# 14_FPGA_SPI.net
KiCad netlist of a schematic drawn in Altium Designer
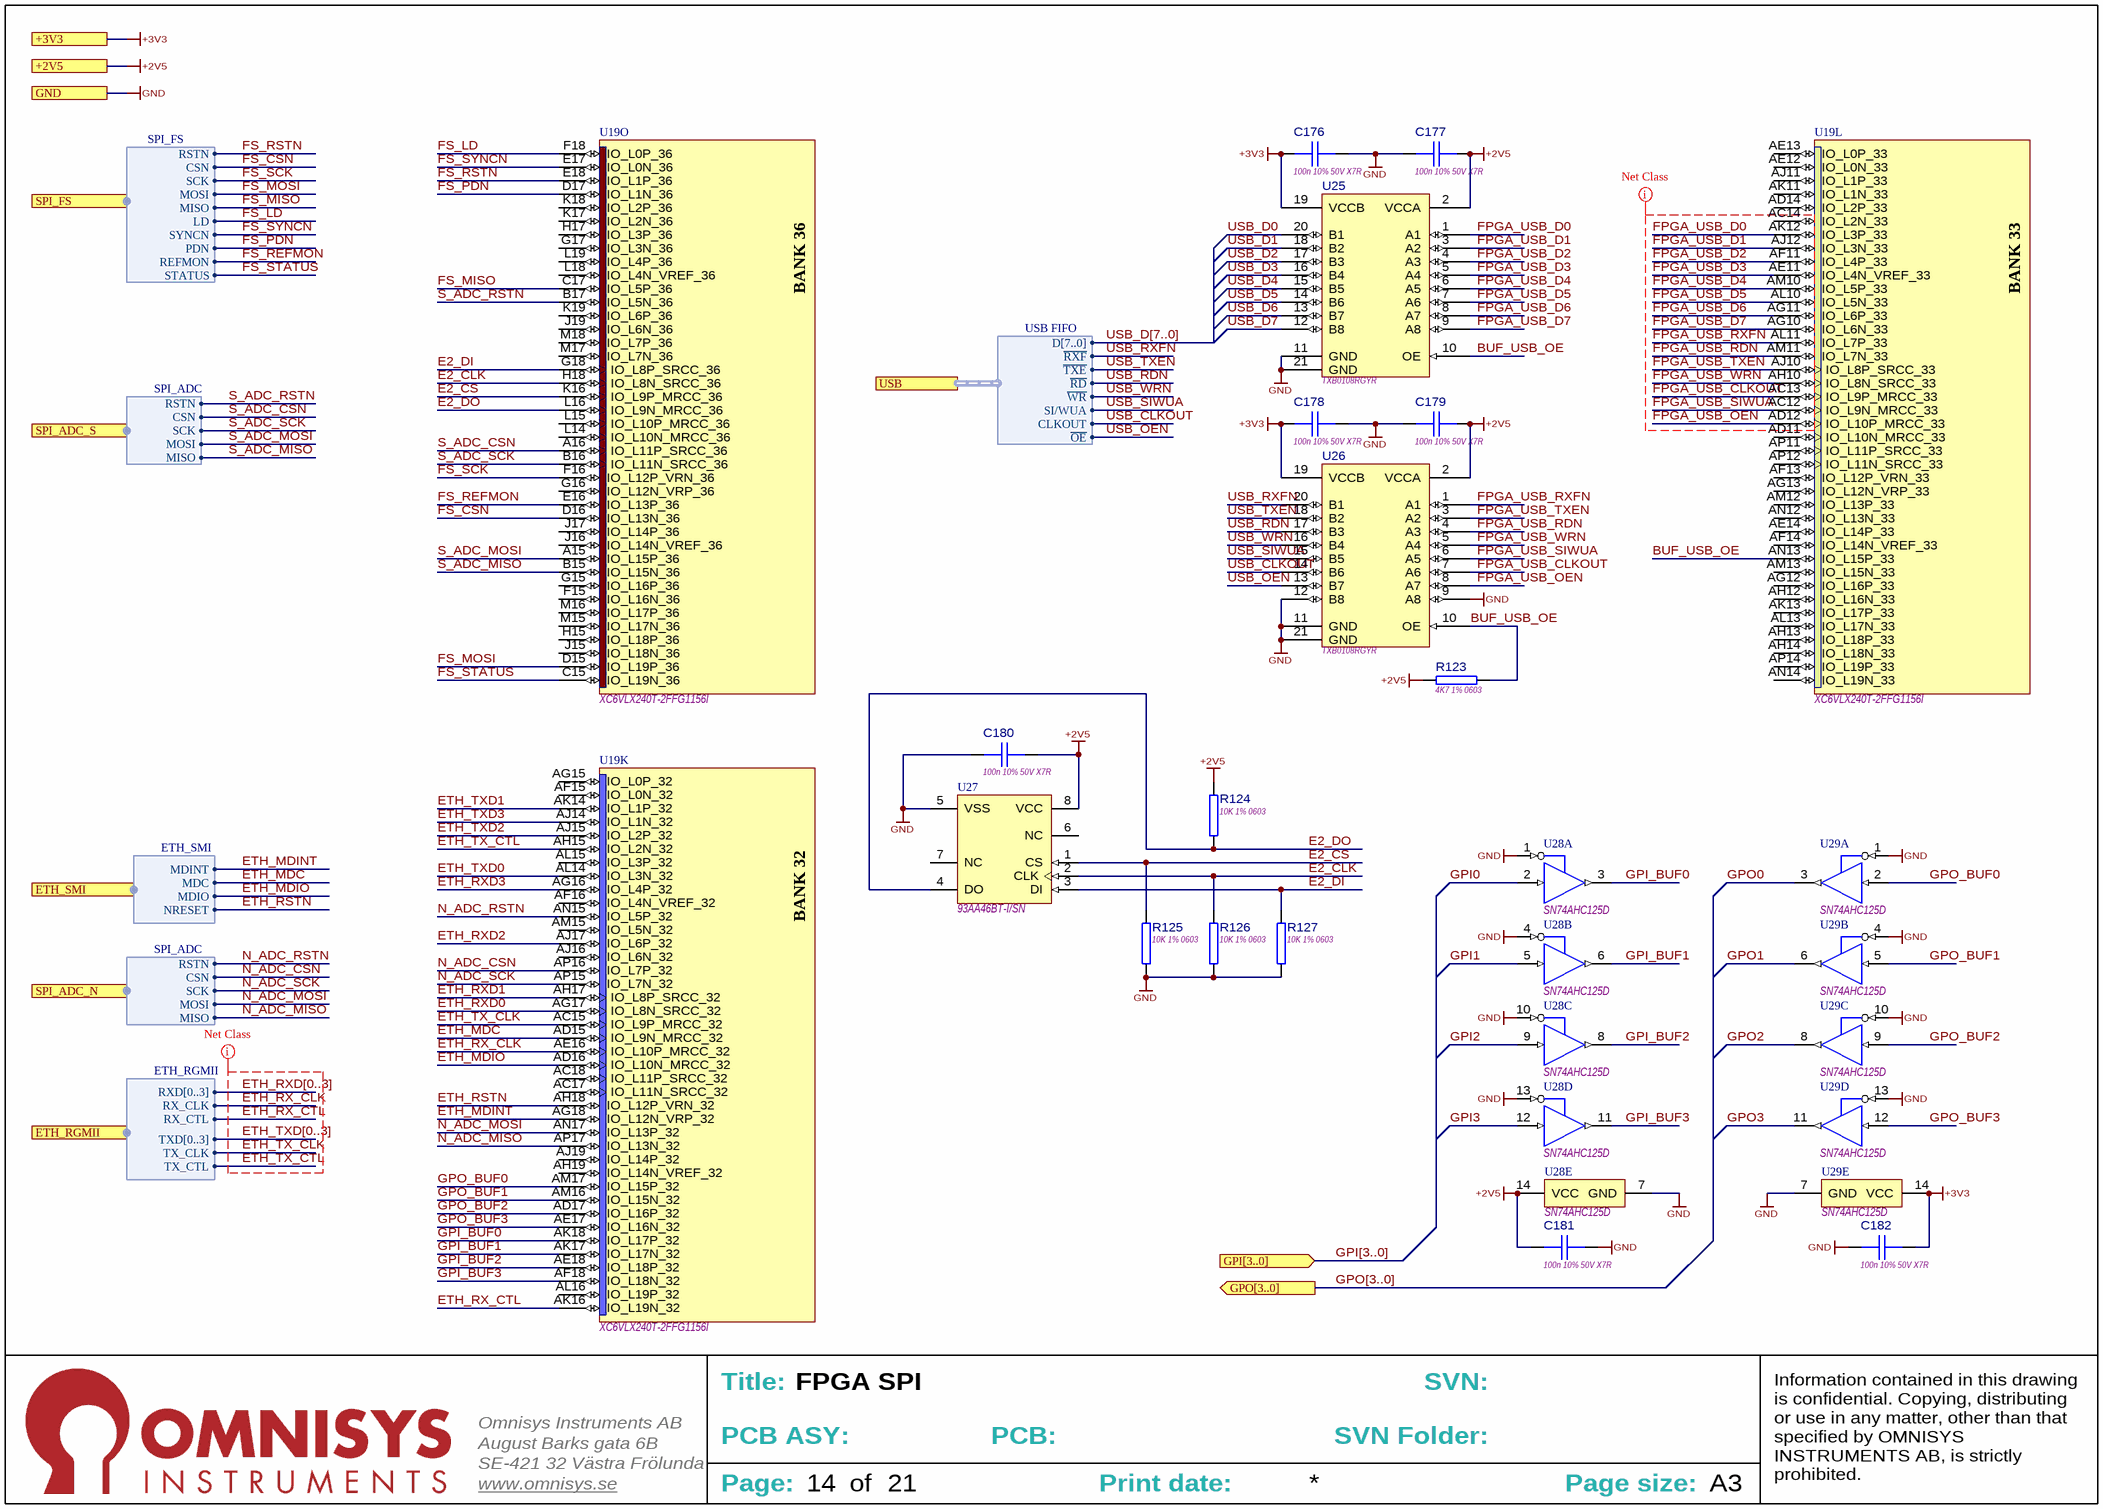
[diagram p0: [14] FPGA_SPI.SchDoc]

(export (version "E")
  (design (tool "Eeschema 10.0.6"))
  (components
    (comp (ref "C176")
      (value "100n 10% 50V X7R")
      (footprint "CAPC1608X90N")
      (description "Ceramic Chip Capacitor, 0603/1608")
      (fields (field (name "TOLERANCE") "10%"))
      (libsource (lib "Omnisys Vault") (part "CAP-2PIN"))
    )
    (comp (ref "C177")
      (value "100n 10% 50V X7R")
      (footprint "CAPC1608X90N")
      (description "Ceramic Chip Capacitor, 0603/1608")
      (fields (field (name "TOLERANCE") "10%"))
      (libsource (lib "Omnisys Vault") (part "CAP-2PIN"))
    )
    (comp (ref "C178")
      (value "100n 10% 50V X7R")
      (footprint "CAPC1608X90N")
      (description "Ceramic Chip Capacitor, 0603/1608")
      (fields (field (name "TOLERANCE") "10%"))
      (libsource (lib "Omnisys Vault") (part "CAP-2PIN"))
    )
    (comp (ref "C179")
      (value "100n 10% 50V X7R")
      (footprint "CAPC1608X90N")
      (description "Ceramic Chip Capacitor, 0603/1608")
      (fields (field (name "TOLERANCE") "10%"))
      (libsource (lib "Omnisys Vault") (part "CAP-2PIN"))
    )
    (comp (ref "C180")
      (value "100n 10% 50V X7R")
      (footprint "CAPC1608X90N")
      (description "Ceramic Chip Capacitor, 0603/1608")
      (fields (field (name "TOLERANCE") "10%"))
      (libsource (lib "Omnisys Vault") (part "CAP-2PIN"))
    )
    (comp (ref "C181")
      (value "100n 10% 50V X7R")
      (footprint "CAPC1608X90N")
      (description "Ceramic Chip Capacitor, 0603/1608")
      (fields (field (name "TOLERANCE") "10%"))
      (libsource (lib "Omnisys Vault") (part "CAP-2PIN"))
    )
    (comp (ref "C182")
      (value "100n 10% 50V X7R")
      (footprint "CAPC1608X90N")
      (description "Ceramic Chip Capacitor, 0603/1608")
      (fields (field (name "TOLERANCE") "10%"))
      (libsource (lib "Omnisys Vault") (part "CAP-2PIN"))
    )
    (comp (ref "R123")
      (value "4K7 1% 0603")
      (footprint "RESC1608N")
      (description "Thick film Chip Resistor, 0603/1608")
      (fields (field (name "POWER") "100mW") (field (name "TOLERANCE") "1%"))
      (libsource (lib "Omnisys Vault") (part "RES-2PIN"))
    )
    (comp (ref "R124")
      (value "10K 1% 0603")
      (footprint "RESC1608N")
      (description "Thick film Chip Resistor, 0603/1608")
      (fields (field (name "POWER") "100mW") (field (name "TOLERANCE") "1%"))
      (libsource (lib "Omnisys Vault") (part "RES-2PIN"))
    )
    (comp (ref "R125")
      (value "10K 1% 0603")
      (footprint "RESC1608N")
      (description "Thick film Chip Resistor, 0603/1608")
      (fields (field (name "POWER") "100mW") (field (name "TOLERANCE") "1%"))
      (libsource (lib "Omnisys Vault") (part "RES-2PIN"))
    )
    (comp (ref "R126")
      (value "10K 1% 0603")
      (footprint "RESC1608N")
      (description "Thick film Chip Resistor, 0603/1608")
      (fields (field (name "POWER") "100mW") (field (name "TOLERANCE") "1%"))
      (libsource (lib "Omnisys Vault") (part "RES-2PIN"))
    )
    (comp (ref "R127")
      (value "10K 1% 0603")
      (footprint "RESC1608N")
      (description "Thick film Chip Resistor, 0603/1608")
      (fields (field (name "POWER") "100mW") (field (name "TOLERANCE") "1%"))
      (libsource (lib "Omnisys Vault") (part "RES-2PIN"))
    )
    (comp (ref "U19")
      (value "XC6VLX240T-2FFG1156I")
      (footprint "FFG1156")
      (description "FPGA Virtex-6 LXT Family 241152 Cells 40nm (CMOS) Technology 1V 1156-Pin FCBGA")
      (libsource (lib "Omnisys Vault") (part "FPGA-XVR6-XC6VXXXXXT-GA1156"))
    )
    (comp (ref "U25")
      (value "TXB0108RGYR")
      (footprint "TXB0108RGYR")
      (description "TEXAS INSTRUMENTS   TXB0108RGYR   TRANSLATOR, VOLTAGE, 8BIT, 20VQFN")
      (libsource (lib "Omnisys Vault") (part "TXB0108RGYR"))
    )
    (comp (ref "U26")
      (value "TXB0108RGYR")
      (footprint "TXB0108RGYR")
      (description "TEXAS INSTRUMENTS   TXB0108RGYR   TRANSLATOR, VOLTAGE, 8BIT, 20VQFN")
      (libsource (lib "Omnisys Vault") (part "TXB0108RGYR"))
    )
    (comp (ref "U27")
      (value "93AA46BT-I/SN")
      (footprint "SOIC127P600X175-8N")
      (description "IC EEPROM 1KBIT 2MHZ 8SOIC")
      (libsource (lib "Omnisys Vault") (part "MEM-SEEPROM-93AA46B-P-8"))
    )
    (comp (ref "U28")
      (value "SN74AHC125D")
      (footprint "SOIC127P600X175-14N")
      (description "Buffer/Line Driver 4-CH Non-Inverting 3-ST CMOS 14-Pin SOIC Tube")
      (libsource (lib "Omnisys Vault") (part "SN74AHC125D"))
    )
    (comp (ref "U29")
      (value "SN74AHC125D")
      (footprint "SOIC127P600X175-14L")
      (description "Buffer/Line Driver 4-CH Non-Inverting 3-ST CMOS 14-Pin SOIC Tube")
      (libsource (lib "") (part "SN74AHC125D_1"))
    )
  )
  (nets
    (net (code "7") (name "+2V5") (class "Default")
      (node (ref "C177") (pin "2") (pinfunction "2_2") (pintype "passive"))
      (node (ref "C179") (pin "2") (pinfunction "2_2") (pintype "passive"))
      (node (ref "C180") (pin "2") (pinfunction "2_2") (pintype "passive"))
      (node (ref "C181") (pin "1") (pinfunction "1_1") (pintype "passive"))
      (node (ref "R123") (pin "2") (pinfunction "2_2") (pintype "passive"))
      (node (ref "R124") (pin "2") (pinfunction "2_2") (pintype "passive"))
      (node (ref "U25") (pin "2") (pinfunction "VCCA_2") (pintype "power_in"))
      (node (ref "U26") (pin "2") (pinfunction "VCCA_2") (pintype "power_in"))
      (node (ref "U27") (pin "8") (pinfunction "VCC_8") (pintype "power_in"))
      (node (ref "U28") (pin "14") (pinfunction "VCC_14") (pintype "power_in"))
    )
    (net (code "8") (name "+3V3") (class "Default")
      (node (ref "C176") (pin "1") (pinfunction "1_1") (pintype "passive"))
      (node (ref "C178") (pin "1") (pinfunction "1_1") (pintype "passive"))
      (node (ref "C182") (pin "1") (pinfunction "1_1") (pintype "passive"))
      (node (ref "U25") (pin "19") (pinfunction "VCCB_19") (pintype "power_in"))
      (node (ref "U26") (pin "19") (pinfunction "VCCB_19") (pintype "power_in"))
      (node (ref "U29") (pin "14") (pinfunction "VCC_14") (pintype "power_in"))
    )
    (net (code "9") (name "/BUF_USB_OE") (class "Default")
      (node (ref "R123") (pin "1") (pinfunction "1_1") (pintype "passive"))
      (node (ref "U19") (pin "AN13") (pinfunction "IO_L15P_33_AN13") (pintype "bidirectional"))
      (node (ref "U25") (pin "10") (pinfunction "OE_10") (pintype "input"))
      (node (ref "U26") (pin "10") (pinfunction "OE_10") (pintype "input"))
    )
    (net (code "10") (name "/E2_CLK") (class "Default")
      (node (ref "R126") (pin "2") (pinfunction "2_2") (pintype "passive"))
      (node (ref "U19") (pin "H18") (pinfunction "IO_L8N_SRCC_36_H18") (pintype "bidirectional"))
      (node (ref "U27") (pin "2") (pinfunction "CLK_2") (pintype "input"))
    )
    (net (code "11") (name "/E2_CS") (class "Default")
      (node (ref "R125") (pin "2") (pinfunction "2_2") (pintype "passive"))
      (node (ref "U19") (pin "K16") (pinfunction "IO_L9P_MRCC_36_K16") (pintype "bidirectional"))
      (node (ref "U27") (pin "1") (pinfunction "CS_1") (pintype "input"))
    )
    (net (code "12") (name "/E2_DI") (class "Default")
      (node (ref "R127") (pin "2") (pinfunction "2_2") (pintype "passive"))
      (node (ref "U19") (pin "G18") (pinfunction "IO_L8P_SRCC_36_G18") (pintype "bidirectional"))
      (node (ref "U27") (pin "3") (pinfunction "DI_3") (pintype "input"))
    )
    (net (code "13") (name "/E2_DO") (class "Default")
      (node (ref "R124") (pin "1") (pinfunction "1_1") (pintype "passive"))
      (node (ref "U19") (pin "L16") (pinfunction "IO_L9N_MRCC_36_L16") (pintype "bidirectional"))
      (node (ref "U27") (pin "4") (pinfunction "DO_4") (pintype "tri_state"))
    )
    (net (code "14") (name "/ETH_MDC") (class "Default")
      (node (ref "U19") (pin "AD15") (pinfunction "IO_L9N_MRCC_32_AD15") (pintype "bidirectional"))
    )
    (net (code "15") (name "/ETH_MDINT") (class "Default")
      (node (ref "U19") (pin "AG18") (pinfunction "IO_L12N_VRP_32_AG18") (pintype "bidirectional"))
    )
    (net (code "16") (name "/ETH_MDIO") (class "Default")
      (node (ref "U19") (pin "AD16") (pinfunction "IO_L10N_MRCC_32_AD16") (pintype "bidirectional"))
    )
    (net (code "18") (name "/ETH_RSTN") (class "Default")
      (node (ref "U19") (pin "AH18") (pinfunction "IO_L12P_VRN_32_AH18") (pintype "bidirectional"))
    )
    (net (code "19") (name "/ETH_RXD0") (class "Default")
      (node (ref "U19") (pin "AG17") (pinfunction "IO_L8N_SRCC_32_AG17") (pintype "bidirectional"))
    )
    (net (code "20") (name "/ETH_RXD1") (class "Default")
      (node (ref "U19") (pin "AH17") (pinfunction "IO_L8P_SRCC_32_AH17") (pintype "bidirectional"))
    )
    (net (code "21") (name "/ETH_RXD2") (class "Default")
      (node (ref "U19") (pin "AJ17") (pinfunction "IO_L6P_32_AJ17") (pintype "bidirectional"))
    )
    (net (code "22") (name "/ETH_RXD3") (class "Default")
      (node (ref "U19") (pin "AG16") (pinfunction "IO_L4P_32_AG16") (pintype "bidirectional"))
    )
    (net (code "24") (name "/ETH_RX_CLK") (class "Default")
      (node (ref "U19") (pin "AE16") (pinfunction "IO_L10P_MRCC_32_AE16") (pintype "bidirectional"))
    )
    (net (code "25") (name "/ETH_RX_CTL") (class "Default")
      (node (ref "U19") (pin "AK16") (pinfunction "IO_L19N_32_AK16") (pintype "bidirectional"))
    )
    (net (code "26") (name "/ETH_TXD0") (class "Default")
      (node (ref "U19") (pin "AL14") (pinfunction "IO_L3N_32_AL14") (pintype "bidirectional"))
    )
    (net (code "27") (name "/ETH_TXD1") (class "Default")
      (node (ref "U19") (pin "AK14") (pinfunction "IO_L1P_32_AK14") (pintype "bidirectional"))
    )
    (net (code "28") (name "/ETH_TXD2") (class "Default")
      (node (ref "U19") (pin "AJ15") (pinfunction "IO_L2P_32_AJ15") (pintype "bidirectional"))
    )
    (net (code "29") (name "/ETH_TXD3") (class "Default")
      (node (ref "U19") (pin "AJ14") (pinfunction "IO_L1N_32_AJ14") (pintype "bidirectional"))
    )
    (net (code "30") (name "/ETH_TX_CLK") (class "Default")
      (node (ref "U19") (pin "AC15") (pinfunction "IO_L9P_MRCC_32_AC15") (pintype "bidirectional"))
    )
    (net (code "31") (name "/ETH_TX_CTL") (class "Default")
      (node (ref "U19") (pin "AH15") (pinfunction "IO_L2N_32_AH15") (pintype "bidirectional"))
    )
    (net (code "32") (name "/FPGA_USB_CLKOUT") (class "Default")
      (node (ref "U19") (pin "AC13") (pinfunction "IO_L9P_MRCC_33_AC13") (pintype "bidirectional"))
      (node (ref "U26") (pin "7") (pinfunction "A6_7") (pintype "bidirectional"))
    )
    (net (code "33") (name "/FPGA_USB_D0") (class "Default")
      (node (ref "U19") (pin "AK12") (pinfunction "IO_L3P_33_AK12") (pintype "bidirectional"))
      (node (ref "U25") (pin "1") (pinfunction "A1_1") (pintype "bidirectional"))
    )
    (net (code "34") (name "/FPGA_USB_D1") (class "Default")
      (node (ref "U19") (pin "AJ12") (pinfunction "IO_L3N_33_AJ12") (pintype "bidirectional"))
      (node (ref "U25") (pin "3") (pinfunction "A2_3") (pintype "bidirectional"))
    )
    (net (code "35") (name "/FPGA_USB_D2") (class "Default")
      (node (ref "U19") (pin "AF11") (pinfunction "IO_L4P_33_AF11") (pintype "bidirectional"))
      (node (ref "U25") (pin "4") (pinfunction "A3_4") (pintype "bidirectional"))
    )
    (net (code "36") (name "/FPGA_USB_D3") (class "Default")
      (node (ref "U19") (pin "AE11") (pinfunction "IO_L4N_VREF_33_AE11") (pintype "bidirectional"))
      (node (ref "U25") (pin "5") (pinfunction "A4_5") (pintype "bidirectional"))
    )
    (net (code "37") (name "/FPGA_USB_D4") (class "Default")
      (node (ref "U19") (pin "AM10") (pinfunction "IO_L5P_33_AM10") (pintype "bidirectional"))
      (node (ref "U25") (pin "6") (pinfunction "A5_6") (pintype "bidirectional"))
    )
    (net (code "38") (name "/FPGA_USB_D5") (class "Default")
      (node (ref "U19") (pin "AL10") (pinfunction "IO_L5N_33_AL10") (pintype "bidirectional"))
      (node (ref "U25") (pin "7") (pinfunction "A6_7") (pintype "bidirectional"))
    )
    (net (code "39") (name "/FPGA_USB_D6") (class "Default")
      (node (ref "U19") (pin "AG11") (pinfunction "IO_L6P_33_AG11") (pintype "bidirectional"))
      (node (ref "U25") (pin "8") (pinfunction "A7_8") (pintype "bidirectional"))
    )
    (net (code "40") (name "/FPGA_USB_D7") (class "Default")
      (node (ref "U19") (pin "AG10") (pinfunction "IO_L6N_33_AG10") (pintype "bidirectional"))
      (node (ref "U25") (pin "9") (pinfunction "A8_9") (pintype "bidirectional"))
    )
    (net (code "41") (name "/FPGA_USB_OEN") (class "Default")
      (node (ref "U19") (pin "AD12") (pinfunction "IO_L10P_MRCC_33_AD12") (pintype "bidirectional"))
      (node (ref "U26") (pin "8") (pinfunction "A7_8") (pintype "bidirectional"))
    )
    (net (code "42") (name "/FPGA_USB_RDN") (class "Default")
      (node (ref "U19") (pin "AM11") (pinfunction "IO_L7N_33_AM11") (pintype "bidirectional"))
      (node (ref "U26") (pin "4") (pinfunction "A3_4") (pintype "bidirectional"))
    )
    (net (code "43") (name "/FPGA_USB_RXFN") (class "Default")
      (node (ref "U19") (pin "AL11") (pinfunction "IO_L7P_33_AL11") (pintype "bidirectional"))
      (node (ref "U26") (pin "1") (pinfunction "A1_1") (pintype "bidirectional"))
    )
    (net (code "44") (name "/FPGA_USB_SIWUA") (class "Default")
      (node (ref "U19") (pin "AC12") (pinfunction "IO_L9N_MRCC_33_AC12") (pintype "bidirectional"))
      (node (ref "U26") (pin "6") (pinfunction "A5_6") (pintype "bidirectional"))
    )
    (net (code "45") (name "/FPGA_USB_TXEN") (class "Default")
      (node (ref "U19") (pin "AJ10") (pinfunction "IO_L8P_SRCC_33_AJ10") (pintype "bidirectional"))
      (node (ref "U26") (pin "3") (pinfunction "A2_3") (pintype "bidirectional"))
    )
    (net (code "46") (name "/FPGA_USB_WRN") (class "Default")
      (node (ref "U19") (pin "AH10") (pinfunction "IO_L8N_SRCC_33_AH10") (pintype "bidirectional"))
      (node (ref "U26") (pin "5") (pinfunction "A4_5") (pintype "bidirectional"))
    )
    (net (code "47") (name "/FS_CSN") (class "Default")
      (node (ref "U19") (pin "D16") (pinfunction "IO_L13N_36_D16") (pintype "bidirectional"))
    )
    (net (code "48") (name "/FS_LD") (class "Default")
      (node (ref "U19") (pin "F18") (pinfunction "IO_L0P_36_F18") (pintype "bidirectional"))
    )
    (net (code "49") (name "/FS_MISO") (class "Default")
      (node (ref "U19") (pin "C17") (pinfunction "IO_L5P_36_C17") (pintype "bidirectional"))
    )
    (net (code "50") (name "/FS_MOSI") (class "Default")
      (node (ref "U19") (pin "D15") (pinfunction "IO_L19P_36_D15") (pintype "bidirectional"))
    )
    (net (code "51") (name "/FS_PDN") (class "Default")
      (node (ref "U19") (pin "D17") (pinfunction "IO_L1N_36_D17") (pintype "bidirectional"))
    )
    (net (code "52") (name "/FS_REFMON") (class "Default")
      (node (ref "U19") (pin "E16") (pinfunction "IO_L13P_36_E16") (pintype "bidirectional"))
    )
    (net (code "53") (name "/FS_RSTN") (class "Default")
      (node (ref "U19") (pin "E18") (pinfunction "IO_L1P_36_E18") (pintype "bidirectional"))
    )
    (net (code "54") (name "/FS_SCK") (class "Default")
      (node (ref "U19") (pin "F16") (pinfunction "IO_L12P_VRN_36_F16") (pintype "bidirectional"))
    )
    (net (code "55") (name "/FS_STATUS") (class "Default")
      (node (ref "U19") (pin "C15") (pinfunction "IO_L19N_36_C15") (pintype "bidirectional"))
    )
    (net (code "56") (name "/FS_SYNCN") (class "Default")
      (node (ref "U19") (pin "E17") (pinfunction "IO_L0N_36_E17") (pintype "bidirectional"))
    )
    (net (code "57") (name "/GPI0") (class "Default")
      (node (ref "U28") (pin "2") (pinfunction "1A_2") (pintype "input"))
    )
    (net (code "58") (name "/GPI1") (class "Default")
      (node (ref "U28") (pin "5") (pinfunction "2A_5") (pintype "input"))
    )
    (net (code "59") (name "/GPI2") (class "Default")
      (node (ref "U28") (pin "9") (pinfunction "3A_9") (pintype "input"))
    )
    (net (code "60") (name "/GPI3") (class "Default")
      (node (ref "U28") (pin "12") (pinfunction "4A_12") (pintype "input"))
    )
    (net (code "62") (name "/GPI_BUF0") (class "Default")
      (node (ref "U19") (pin "AK18") (pinfunction "IO_L17P_32_AK18") (pintype "bidirectional"))
      (node (ref "U28") (pin "3") (pinfunction "1Y_3") (pintype "output"))
    )
    (net (code "63") (name "/GPI_BUF1") (class "Default")
      (node (ref "U19") (pin "AK17") (pinfunction "IO_L17N_32_AK17") (pintype "bidirectional"))
      (node (ref "U28") (pin "6") (pinfunction "2Y_6") (pintype "output"))
    )
    (net (code "64") (name "/GPI_BUF2") (class "Default")
      (node (ref "U19") (pin "AE18") (pinfunction "IO_L18P_32_AE18") (pintype "bidirectional"))
      (node (ref "U28") (pin "8") (pinfunction "3Y_8") (pintype "output"))
    )
    (net (code "65") (name "/GPI_BUF3") (class "Default")
      (node (ref "U19") (pin "AF18") (pinfunction "IO_L18N_32_AF18") (pintype "bidirectional"))
      (node (ref "U28") (pin "11") (pinfunction "4Y_11") (pintype "output"))
    )
    (net (code "66") (name "/GPO0") (class "Default")
      (node (ref "U29") (pin "3") (pinfunction "1Y_3") (pintype "output"))
    )
    (net (code "67") (name "/GPO1") (class "Default")
      (node (ref "U29") (pin "6") (pinfunction "2Y_6") (pintype "output"))
    )
    (net (code "68") (name "/GPO2") (class "Default")
      (node (ref "U29") (pin "8") (pinfunction "3Y_8") (pintype "output"))
    )
    (net (code "69") (name "/GPO3") (class "Default")
      (node (ref "U29") (pin "11") (pinfunction "4Y_11") (pintype "output"))
    )
    (net (code "71") (name "/GPO_BUF0") (class "Default")
      (node (ref "U19") (pin "AM17") (pinfunction "IO_L15P_32_AM17") (pintype "bidirectional"))
      (node (ref "U29") (pin "2") (pinfunction "1A_2") (pintype "input"))
    )
    (net (code "72") (name "/GPO_BUF1") (class "Default")
      (node (ref "U19") (pin "AM16") (pinfunction "IO_L15N_32_AM16") (pintype "bidirectional"))
      (node (ref "U29") (pin "5") (pinfunction "2A_5") (pintype "input"))
    )
    (net (code "73") (name "/GPO_BUF2") (class "Default")
      (node (ref "U19") (pin "AD17") (pinfunction "IO_L16P_32_AD17") (pintype "bidirectional"))
      (node (ref "U29") (pin "9") (pinfunction "3A_9") (pintype "input"))
    )
    (net (code "74") (name "/GPO_BUF3") (class "Default")
      (node (ref "U19") (pin "AE17") (pinfunction "IO_L16N_32_AE17") (pintype "bidirectional"))
      (node (ref "U29") (pin "12") (pinfunction "4A_12") (pintype "input"))
    )
    (net (code "75") (name "/N_ADC_CSN") (class "Default")
      (node (ref "U19") (pin "AP16") (pinfunction "IO_L7P_32_AP16") (pintype "bidirectional"))
    )
    (net (code "76") (name "/N_ADC_MISO") (class "Default")
      (node (ref "U19") (pin "AP17") (pinfunction "IO_L13N_32_AP17") (pintype "bidirectional"))
    )
    (net (code "77") (name "/N_ADC_MOSI") (class "Default")
      (node (ref "U19") (pin "AN17") (pinfunction "IO_L13P_32_AN17") (pintype "bidirectional"))
    )
    (net (code "78") (name "/N_ADC_RSTN") (class "Default")
      (node (ref "U19") (pin "AN15") (pinfunction "IO_L5P_32_AN15") (pintype "bidirectional"))
    )
    (net (code "79") (name "/N_ADC_SCK") (class "Default")
      (node (ref "U19") (pin "AP15") (pinfunction "IO_L7N_32_AP15") (pintype "bidirectional"))
    )
    (net (code "80") (name "/S_ADC_CSN") (class "Default")
      (node (ref "U19") (pin "A16") (pinfunction "IO_L11P_SRCC_36_A16") (pintype "bidirectional"))
    )
    (net (code "81") (name "/S_ADC_MISO") (class "Default")
      (node (ref "U19") (pin "B15") (pinfunction "IO_L15N_36_B15") (pintype "bidirectional"))
    )
    (net (code "82") (name "/S_ADC_MOSI") (class "Default")
      (node (ref "U19") (pin "A15") (pinfunction "IO_L15P_36_A15") (pintype "bidirectional"))
    )
    (net (code "83") (name "/S_ADC_RSTN") (class "Default")
      (node (ref "U19") (pin "B17") (pinfunction "IO_L5N_36_B17") (pintype "bidirectional"))
    )
    (net (code "84") (name "/S_ADC_SCK") (class "Default")
      (node (ref "U19") (pin "B16") (pinfunction "IO_L11N_SRCC_36_B16") (pintype "bidirectional"))
    )
    (net (code "85") (name "/USB_CLKOUT") (class "Default")
      (node (ref "U26") (pin "14") (pinfunction "B6_14") (pintype "bidirectional"))
    )
    (net (code "86") (name "/USB_D0") (class "Default")
      (node (ref "U25") (pin "20") (pinfunction "B1_20") (pintype "bidirectional"))
    )
    (net (code "87") (name "/USB_D1") (class "Default")
      (node (ref "U25") (pin "18") (pinfunction "B2_18") (pintype "bidirectional"))
    )
    (net (code "88") (name "/USB_D2") (class "Default")
      (node (ref "U25") (pin "17") (pinfunction "B3_17") (pintype "bidirectional"))
    )
    (net (code "89") (name "/USB_D3") (class "Default")
      (node (ref "U25") (pin "16") (pinfunction "B4_16") (pintype "bidirectional"))
    )
    (net (code "90") (name "/USB_D4") (class "Default")
      (node (ref "U25") (pin "15") (pinfunction "B5_15") (pintype "bidirectional"))
    )
    (net (code "91") (name "/USB_D5") (class "Default")
      (node (ref "U25") (pin "14") (pinfunction "B6_14") (pintype "bidirectional"))
    )
    (net (code "92") (name "/USB_D6") (class "Default")
      (node (ref "U25") (pin "13") (pinfunction "B7_13") (pintype "bidirectional"))
    )
    (net (code "93") (name "/USB_D7") (class "Default")
      (node (ref "U25") (pin "12") (pinfunction "B8_12") (pintype "bidirectional"))
    )
    (net (code "95") (name "/USB_OEN") (class "Default")
      (node (ref "U26") (pin "13") (pinfunction "B7_13") (pintype "bidirectional"))
    )
    (net (code "96") (name "/USB_RDN") (class "Default")
      (node (ref "U26") (pin "17") (pinfunction "B3_17") (pintype "bidirectional"))
    )
    (net (code "97") (name "/USB_RXFN") (class "Default")
      (node (ref "U26") (pin "20") (pinfunction "B1_20") (pintype "bidirectional"))
    )
    (net (code "98") (name "/USB_SIWUA") (class "Default")
      (node (ref "U26") (pin "15") (pinfunction "B5_15") (pintype "bidirectional"))
    )
    (net (code "99") (name "/USB_TXEN") (class "Default")
      (node (ref "U26") (pin "18") (pinfunction "B2_18") (pintype "bidirectional"))
    )
    (net (code "100") (name "/USB_WRN") (class "Default")
      (node (ref "U26") (pin "16") (pinfunction "B4_16") (pintype "bidirectional"))
    )
    (net (code "106") (name "GND") (class "Default")
      (node (ref "C176") (pin "2") (pinfunction "2_2") (pintype "passive"))
      (node (ref "C177") (pin "1") (pinfunction "1_1") (pintype "passive"))
      (node (ref "C178") (pin "2") (pinfunction "2_2") (pintype "passive"))
      (node (ref "C179") (pin "1") (pinfunction "1_1") (pintype "passive"))
      (node (ref "C180") (pin "1") (pinfunction "1_1") (pintype "passive"))
      (node (ref "C181") (pin "2") (pinfunction "2_2") (pintype "passive"))
      (node (ref "C182") (pin "2") (pinfunction "2_2") (pintype "passive"))
      (node (ref "R125") (pin "1") (pinfunction "1_1") (pintype "passive"))
      (node (ref "R126") (pin "1") (pinfunction "1_1") (pintype "passive"))
      (node (ref "R127") (pin "1") (pinfunction "1_1") (pintype "passive"))
      (node (ref "U25") (pin "11") (pinfunction "GND_11") (pintype "power_in"))
      (node (ref "U25") (pin "21") (pinfunction "GND_21") (pintype "power_in"))
      (node (ref "U26") (pin "11") (pinfunction "GND_11") (pintype "power_in"))
      (node (ref "U26") (pin "12") (pinfunction "B8_12") (pintype "bidirectional"))
      (node (ref "U26") (pin "21") (pinfunction "GND_21") (pintype "power_in"))
      (node (ref "U26") (pin "9") (pinfunction "A8_9") (pintype "bidirectional"))
      (node (ref "U27") (pin "5") (pinfunction "VSS_5") (pintype "power_in"))
      (node (ref "U28") (pin "1") (pinfunction "1OE#_1") (pintype "input"))
      (node (ref "U28") (pin "10") (pinfunction "3OE#_10") (pintype "input"))
      (node (ref "U28") (pin "13") (pinfunction "4OE#_13") (pintype "input"))
      (node (ref "U28") (pin "4") (pinfunction "2OE#_4") (pintype "input"))
      (node (ref "U28") (pin "7") (pinfunction "GND_7") (pintype "power_in"))
      (node (ref "U29") (pin "1") (pinfunction "1OE#_1") (pintype "input"))
      (node (ref "U29") (pin "10") (pinfunction "3OE#_10") (pintype "input"))
      (node (ref "U29") (pin "13") (pinfunction "4OE#_13") (pintype "input"))
      (node (ref "U29") (pin "4") (pinfunction "2OE#_4") (pintype "input"))
      (node (ref "U29") (pin "7") (pinfunction "GND_7") (pintype "power_in"))
    )
    (net (code "107") (name "unconnected-(U19K-IO_L0N_32-PadAF15)") (class "Default")
      (node (ref "U19") (pin "AF15") (pinfunction "IO_L0N_32_AF15") (pintype "bidirectional"))
    )
    (net (code "108") (name "unconnected-(U19K-IO_L0P_32-PadAG15)") (class "Default")
      (node (ref "U19") (pin "AG15") (pinfunction "IO_L0P_32_AG15") (pintype "bidirectional"))
    )
    (net (code "109") (name "unconnected-(U19K-IO_L3P_32-PadAL15)") (class "Default")
      (node (ref "U19") (pin "AL15") (pinfunction "IO_L3P_32_AL15") (pintype "bidirectional"))
    )
    (net (code "110") (name "unconnected-(U19K-IO_L4N_VREF_32-PadAF16)") (class "Default")
      (node (ref "U19") (pin "AF16") (pinfunction "IO_L4N_VREF_32_AF16") (pintype "bidirectional"))
    )
    (net (code "111") (name "unconnected-(U19K-IO_L5N_32-PadAM15)") (class "Default")
      (node (ref "U19") (pin "AM15") (pinfunction "IO_L5N_32_AM15") (pintype "bidirectional"))
    )
    (net (code "112") (name "unconnected-(U19K-IO_L6N_32-PadAJ16)") (class "Default")
      (node (ref "U19") (pin "AJ16") (pinfunction "IO_L6N_32_AJ16") (pintype "bidirectional"))
    )
    (net (code "113") (name "unconnected-(U19K-IO_L11N_SRCC_32-PadAC17)") (class "Default")
      (node (ref "U19") (pin "AC17") (pinfunction "IO_L11N_SRCC_32_AC17") (pintype "bidirectional"))
    )
    (net (code "114") (name "unconnected-(U19K-IO_L11P_SRCC_32-PadAC18)") (class "Default")
      (node (ref "U19") (pin "AC18") (pinfunction "IO_L11P_SRCC_32_AC18") (pintype "bidirectional"))
    )
    (net (code "115") (name "unconnected-(U19K-IO_L14N_VREF_32-PadAH19)") (class "Default")
      (node (ref "U19") (pin "AH19") (pinfunction "IO_L14N_VREF_32_AH19") (pintype "bidirectional"))
    )
    (net (code "116") (name "unconnected-(U19K-IO_L14P_32-PadAJ19)") (class "Default")
      (node (ref "U19") (pin "AJ19") (pinfunction "IO_L14P_32_AJ19") (pintype "bidirectional"))
    )
    (net (code "117") (name "unconnected-(U19K-IO_L19P_32-PadAL16)") (class "Default")
      (node (ref "U19") (pin "AL16") (pinfunction "IO_L19P_32_AL16") (pintype "bidirectional"))
    )
    (net (code "118") (name "unconnected-(U19L-IO_L0N_33-PadAE12)") (class "Default")
      (node (ref "U19") (pin "AE12") (pinfunction "IO_L0N_33_AE12") (pintype "bidirectional"))
    )
    (net (code "119") (name "unconnected-(U19L-IO_L0P_33-PadAE13)") (class "Default")
      (node (ref "U19") (pin "AE13") (pinfunction "IO_L0P_33_AE13") (pintype "bidirectional"))
    )
    (net (code "120") (name "unconnected-(U19L-IO_L1N_33-PadAK11)") (class "Default")
      (node (ref "U19") (pin "AK11") (pinfunction "IO_L1N_33_AK11") (pintype "bidirectional"))
    )
    (net (code "121") (name "unconnected-(U19L-IO_L1P_33-PadAJ11)") (class "Default")
      (node (ref "U19") (pin "AJ11") (pinfunction "IO_L1P_33_AJ11") (pintype "bidirectional"))
    )
    (net (code "122") (name "unconnected-(U19L-IO_L2N_33-PadAC14)") (class "Default")
      (node (ref "U19") (pin "AC14") (pinfunction "IO_L2N_33_AC14") (pintype "bidirectional"))
    )
    (net (code "123") (name "unconnected-(U19L-IO_L2P_33-PadAD14)") (class "Default")
      (node (ref "U19") (pin "AD14") (pinfunction "IO_L2P_33_AD14") (pintype "bidirectional"))
    )
    (net (code "124") (name "unconnected-(U19L-IO_L10N_MRCC_33-PadAD11)") (class "Default")
      (node (ref "U19") (pin "AD11") (pinfunction "IO_L10N_MRCC_33_AD11") (pintype "bidirectional"))
    )
    (net (code "125") (name "unconnected-(U19L-IO_L11N_SRCC_33-PadAP12)") (class "Default")
      (node (ref "U19") (pin "AP12") (pinfunction "IO_L11N_SRCC_33_AP12") (pintype "bidirectional"))
    )
    (net (code "126") (name "unconnected-(U19L-IO_L11P_SRCC_33-PadAP11)") (class "Default")
      (node (ref "U19") (pin "AP11") (pinfunction "IO_L11P_SRCC_33_AP11") (pintype "bidirectional"))
    )
    (net (code "127") (name "unconnected-(U19L-IO_L12N_VRP_33-PadAG13)") (class "Default")
      (node (ref "U19") (pin "AG13") (pinfunction "IO_L12N_VRP_33_AG13") (pintype "bidirectional"))
    )
    (net (code "128") (name "unconnected-(U19L-IO_L12P_VRN_33-PadAF13)") (class "Default")
      (node (ref "U19") (pin "AF13") (pinfunction "IO_L12P_VRN_33_AF13") (pintype "bidirectional"))
    )
    (net (code "129") (name "unconnected-(U19L-IO_L13N_33-PadAN12)") (class "Default")
      (node (ref "U19") (pin "AN12") (pinfunction "IO_L13N_33_AN12") (pintype "bidirectional"))
    )
    (net (code "130") (name "unconnected-(U19L-IO_L13P_33-PadAM12)") (class "Default")
      (node (ref "U19") (pin "AM12") (pinfunction "IO_L13P_33_AM12") (pintype "bidirectional"))
    )
    (net (code "131") (name "unconnected-(U19L-IO_L14N_VREF_33-PadAF14)") (class "Default")
      (node (ref "U19") (pin "AF14") (pinfunction "IO_L14N_VREF_33_AF14") (pintype "bidirectional"))
    )
    (net (code "132") (name "unconnected-(U19L-IO_L14P_33-PadAE14)") (class "Default")
      (node (ref "U19") (pin "AE14") (pinfunction "IO_L14P_33_AE14") (pintype "bidirectional"))
    )
    (net (code "133") (name "unconnected-(U19L-IO_L15N_33-PadAM13)") (class "Default")
      (node (ref "U19") (pin "AM13") (pinfunction "IO_L15N_33_AM13") (pintype "bidirectional"))
    )
    (net (code "134") (name "unconnected-(U19L-IO_L16N_33-PadAH12)") (class "Default")
      (node (ref "U19") (pin "AH12") (pinfunction "IO_L16N_33_AH12") (pintype "bidirectional"))
    )
    (net (code "135") (name "unconnected-(U19L-IO_L16P_33-PadAG12)") (class "Default")
      (node (ref "U19") (pin "AG12") (pinfunction "IO_L16P_33_AG12") (pintype "bidirectional"))
    )
    (net (code "136") (name "unconnected-(U19L-IO_L17N_33-PadAL13)") (class "Default")
      (node (ref "U19") (pin "AL13") (pinfunction "IO_L17N_33_AL13") (pintype "bidirectional"))
    )
    (net (code "137") (name "unconnected-(U19L-IO_L17P_33-PadAK13)") (class "Default")
      (node (ref "U19") (pin "AK13") (pinfunction "IO_L17P_33_AK13") (pintype "bidirectional"))
    )
    (net (code "138") (name "unconnected-(U19L-IO_L18N_33-PadAH14)") (class "Default")
      (node (ref "U19") (pin "AH14") (pinfunction "IO_L18N_33_AH14") (pintype "bidirectional"))
    )
    (net (code "139") (name "unconnected-(U19L-IO_L18P_33-PadAH13)") (class "Default")
      (node (ref "U19") (pin "AH13") (pinfunction "IO_L18P_33_AH13") (pintype "bidirectional"))
    )
    (net (code "140") (name "unconnected-(U19L-IO_L19N_33-PadAN14)") (class "Default")
      (node (ref "U19") (pin "AN14") (pinfunction "IO_L19N_33_AN14") (pintype "bidirectional"))
    )
    (net (code "141") (name "unconnected-(U19L-IO_L19P_33-PadAP14)") (class "Default")
      (node (ref "U19") (pin "AP14") (pinfunction "IO_L19P_33_AP14") (pintype "bidirectional"))
    )
    (net (code "142") (name "unconnected-(U19O-IO_L2N_36-PadK17)") (class "Default")
      (node (ref "U19") (pin "K17") (pinfunction "IO_L2N_36_K17") (pintype "bidirectional"))
    )
    (net (code "143") (name "unconnected-(U19O-IO_L2P_36-PadK18)") (class "Default")
      (node (ref "U19") (pin "K18") (pinfunction "IO_L2P_36_K18") (pintype "bidirectional"))
    )
    (net (code "144") (name "unconnected-(U19O-IO_L3N_36-PadG17)") (class "Default")
      (node (ref "U19") (pin "G17") (pinfunction "IO_L3N_36_G17") (pintype "bidirectional"))
    )
    (net (code "145") (name "unconnected-(U19O-IO_L3P_36-PadH17)") (class "Default")
      (node (ref "U19") (pin "H17") (pinfunction "IO_L3P_36_H17") (pintype "bidirectional"))
    )
    (net (code "146") (name "unconnected-(U19O-IO_L4N_VREF_36-PadL18)") (class "Default")
      (node (ref "U19") (pin "L18") (pinfunction "IO_L4N_VREF_36_L18") (pintype "bidirectional"))
    )
    (net (code "147") (name "unconnected-(U19O-IO_L4P_36-PadL19)") (class "Default")
      (node (ref "U19") (pin "L19") (pinfunction "IO_L4P_36_L19") (pintype "bidirectional"))
    )
    (net (code "148") (name "unconnected-(U19O-IO_L6N_36-PadJ19)") (class "Default")
      (node (ref "U19") (pin "J19") (pinfunction "IO_L6N_36_J19") (pintype "bidirectional"))
    )
    (net (code "149") (name "unconnected-(U19O-IO_L6P_36-PadK19)") (class "Default")
      (node (ref "U19") (pin "K19") (pinfunction "IO_L6P_36_K19") (pintype "bidirectional"))
    )
    (net (code "150") (name "unconnected-(U19O-IO_L7N_36-PadM17)") (class "Default")
      (node (ref "U19") (pin "M17") (pinfunction "IO_L7N_36_M17") (pintype "bidirectional"))
    )
    (net (code "151") (name "unconnected-(U19O-IO_L7P_36-PadM18)") (class "Default")
      (node (ref "U19") (pin "M18") (pinfunction "IO_L7P_36_M18") (pintype "bidirectional"))
    )
    (net (code "152") (name "unconnected-(U19O-IO_L10N_MRCC_36-PadL14)") (class "Default")
      (node (ref "U19") (pin "L14") (pinfunction "IO_L10N_MRCC_36_L14") (pintype "bidirectional"))
    )
    (net (code "153") (name "unconnected-(U19O-IO_L10P_MRCC_36-PadL15)") (class "Default")
      (node (ref "U19") (pin "L15") (pinfunction "IO_L10P_MRCC_36_L15") (pintype "bidirectional"))
    )
    (net (code "154") (name "unconnected-(U19O-IO_L12N_VRP_36-PadG16)") (class "Default")
      (node (ref "U19") (pin "G16") (pinfunction "IO_L12N_VRP_36_G16") (pintype "bidirectional"))
    )
    (net (code "155") (name "unconnected-(U19O-IO_L14N_VREF_36-PadJ16)") (class "Default")
      (node (ref "U19") (pin "J16") (pinfunction "IO_L14N_VREF_36_J16") (pintype "bidirectional"))
    )
    (net (code "156") (name "unconnected-(U19O-IO_L14P_36-PadJ17)") (class "Default")
      (node (ref "U19") (pin "J17") (pinfunction "IO_L14P_36_J17") (pintype "bidirectional"))
    )
    (net (code "157") (name "unconnected-(U19O-IO_L16N_36-PadF15)") (class "Default")
      (node (ref "U19") (pin "F15") (pinfunction "IO_L16N_36_F15") (pintype "bidirectional"))
    )
    (net (code "158") (name "unconnected-(U19O-IO_L16P_36-PadG15)") (class "Default")
      (node (ref "U19") (pin "G15") (pinfunction "IO_L16P_36_G15") (pintype "bidirectional"))
    )
    (net (code "159") (name "unconnected-(U19O-IO_L17N_36-PadM15)") (class "Default")
      (node (ref "U19") (pin "M15") (pinfunction "IO_L17N_36_M15") (pintype "bidirectional"))
    )
    (net (code "160") (name "unconnected-(U19O-IO_L17P_36-PadM16)") (class "Default")
      (node (ref "U19") (pin "M16") (pinfunction "IO_L17P_36_M16") (pintype "bidirectional"))
    )
    (net (code "161") (name "unconnected-(U19O-IO_L18N_36-PadJ15)") (class "Default")
      (node (ref "U19") (pin "J15") (pinfunction "IO_L18N_36_J15") (pintype "bidirectional"))
    )
    (net (code "162") (name "unconnected-(U19O-IO_L18P_36-PadH15)") (class "Default")
      (node (ref "U19") (pin "H15") (pinfunction "IO_L18P_36_H15") (pintype "bidirectional"))
    )
    (net (code "163") (name "unconnected-(U27-NC-Pad6)") (class "Default")
      (node (ref "U27") (pin "6") (pinfunction "NC_6") (pintype "passive"))
    )
    (net (code "164") (name "unconnected-(U27-NC-Pad7)") (class "Default")
      (node (ref "U27") (pin "7") (pinfunction "NC_7") (pintype "passive"))
    )
  )
)
